# VisualightMicroDIY_038_gnd.net
KiCad netlist of a schematic drawn in EAGLE
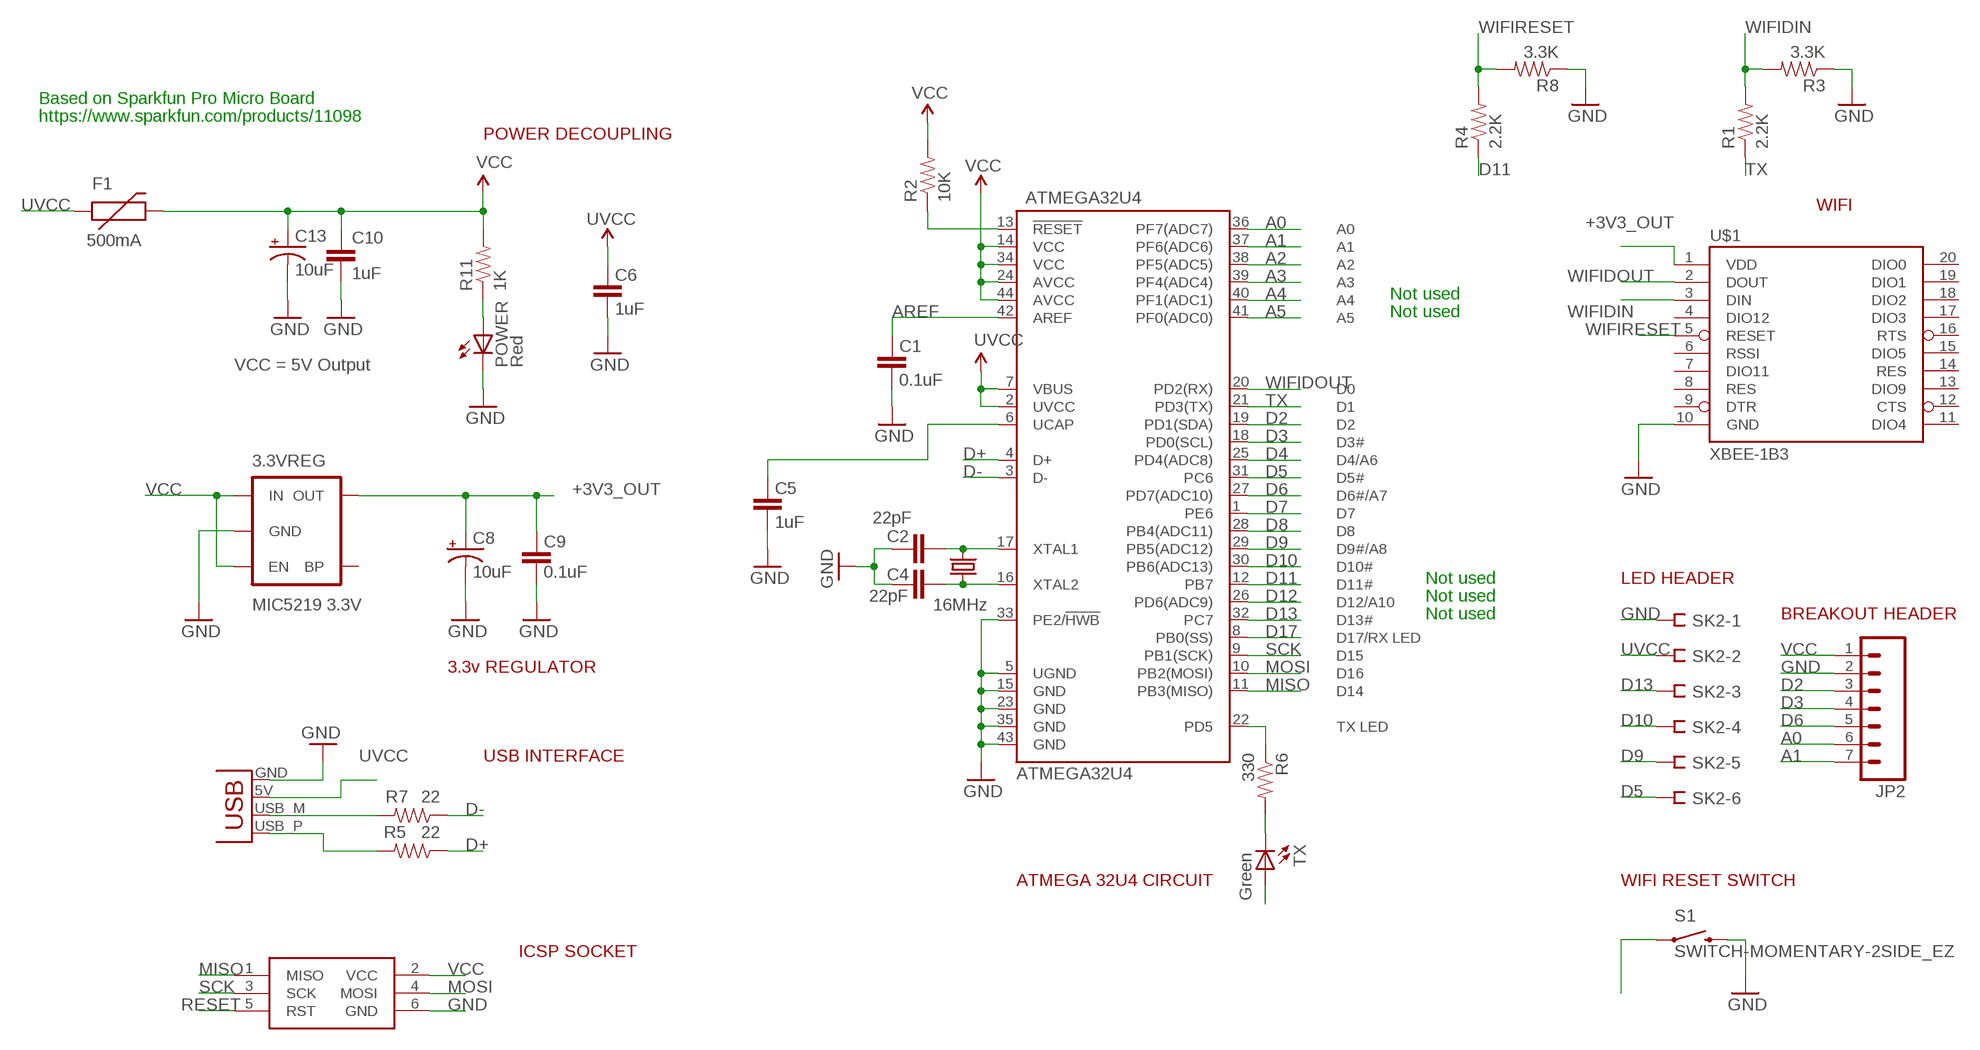
[diagram p0: schematic, sheet 1]

(export (version "E")
  (design (tool "Eeschema 10.0.6"))
  (components
    (comp (ref "3.3VREG")
      (value "MIC5219 3.3V")
      (footprint "eagle-import:SOT23-5")
      (libsource (lib "eagle-import") (part "V_REG_MIC52193.3V"))
    )
    (comp (ref "ATMEGA32U4")
      (value "ATMEGA32U4")
      (footprint "eagle-import:SPARKFUN-DIGITALIC_TQFP44")
      (libsource (lib "eagle-import") (part "ATMEGA32U4TQFP"))
    )
    (comp (ref "C1")
      (value "0.1uF")
      (footprint "eagle-import:0402-CAP")
      (libsource (lib "eagle-import") (part "CAP0402-CAP"))
    )
    (comp (ref "C2")
      (value "22pF")
      (footprint "eagle-import:0402-CAP")
      (libsource (lib "eagle-import") (part "CAP0402-CAP"))
    )
    (comp (ref "C4")
      (value "22pF")
      (footprint "eagle-import:0402-CAP")
      (libsource (lib "eagle-import") (part "CAP0402-CAP"))
    )
    (comp (ref "C5")
      (value "1uF")
      (footprint "eagle-import:0402-CAP")
      (libsource (lib "eagle-import") (part "CAP0402-CAP"))
    )
    (comp (ref "C6")
      (value "1uF")
      (footprint "eagle-import:0402-CAP")
      (libsource (lib "eagle-import") (part "CAP0402-CAP"))
    )
    (comp (ref "C8")
      (value "10uF")
      (footprint "eagle-import:EIA3216")
      (libsource (lib "eagle-import") (part "CAP_POL1206"))
    )
    (comp (ref "C9")
      (value "0.1uF")
      (footprint "eagle-import:0402-CAP")
      (libsource (lib "eagle-import") (part "CAP0402-CAP"))
    )
    (comp (ref "C10")
      (value "1uF")
      (footprint "eagle-import:0402-CAP")
      (libsource (lib "eagle-import") (part "CAP0402-CAP"))
    )
    (comp (ref "C13")
      (value "10uF")
      (footprint "eagle-import:EIA3216")
      (libsource (lib "eagle-import") (part "CAP_POL1206"))
    )
    (comp (ref "F1")
      (value "500mA")
      (footprint "eagle-import:PTC-1206")
      (libsource (lib "eagle-import") (part "PTCSMD"))
    )
    (comp (ref "ISP1")
      (value "AVRISP-6")
      (footprint "eagle-import:AVRISP")
      (libsource (lib "eagle-import") (part "AVRISP-6"))
    )
    (comp (ref "JP2")
      (value "M07")
      (footprint "eagle-import:1X07")
      (libsource (lib "eagle-import") (part "M07"))
    )
    (comp (ref "POWER")
      (value "Red")
      (footprint "eagle-import:LED-0603")
      (libsource (lib "eagle-import") (part "LED0603"))
    )
    (comp (ref "R1")
      (value "2.2K")
      (footprint "eagle-import:0402-RES")
      (libsource (lib "eagle-import") (part "RESISTOR0402-RES"))
    )
    (comp (ref "R2")
      (value "10K")
      (footprint "eagle-import:0402-RES")
      (libsource (lib "eagle-import") (part "RESISTOR0402-RES"))
    )
    (comp (ref "R3")
      (value "3.3K")
      (footprint "eagle-import:0402-RES")
      (libsource (lib "eagle-import") (part "RESISTOR0402-RES"))
    )
    (comp (ref "R4")
      (value "2.2K")
      (footprint "eagle-import:0402-RES")
      (libsource (lib "eagle-import") (part "RESISTOR0402-RES"))
    )
    (comp (ref "R5")
      (value "22")
      (footprint "eagle-import:0402-RES")
      (libsource (lib "eagle-import") (part "RESISTOR0402-RES"))
    )
    (comp (ref "R6")
      (value "330")
      (footprint "eagle-import:0402-RES")
      (libsource (lib "eagle-import") (part "RESISTOR0402-RES"))
    )
    (comp (ref "R7")
      (value "22")
      (footprint "eagle-import:0402-RES")
      (libsource (lib "eagle-import") (part "RESISTOR0402-RES"))
    )
    (comp (ref "R8")
      (value "3.3K")
      (footprint "eagle-import:0402-RES")
      (libsource (lib "eagle-import") (part "RESISTOR0402-RES"))
    )
    (comp (ref "R11")
      (value "1K")
      (footprint "eagle-import:0402-RES")
      (libsource (lib "eagle-import") (part "RESISTOR0402-RES"))
    )
    (comp (ref "S1")
      (value "SWITCH-MOMENTARY-2SIDE_EZ")
      (footprint "eagle-import:TACTILE-PTH-SIDEEZ")
      (libsource (lib "eagle-import") (part "SWITCH-MOMENTARY-2SIDE_EZ"))
    )
    (comp (ref "SK2")
      (value "DF3-06S")
      (footprint "eagle-import:DF3S-06")
      (libsource (lib "eagle-import") (part "DF3-06S"))
    )
    (comp (ref "TX")
      (value "Green")
      (footprint "eagle-import:LED-0603")
      (libsource (lib "eagle-import") (part "LED0603"))
    )
    (comp (ref "U$1")
      (value "XBEE-1B3")
      (footprint "eagle-import:XBEE-SMD")
      (libsource (lib "eagle-import") (part "XBEE-1B3"))
    )
    (comp (ref "X2")
      (value "USBPCB")
      (footprint "eagle-import:USB-A-PCB")
      (libsource (lib "eagle-import") (part "USBPCB"))
    )
    (comp (ref "Y1")
      (value "16MHz")
      (footprint "eagle-import:CRYSTAL-SMD-5X3")
      (libsource (lib "eagle-import") (part "CRYSTAL5X3"))
    )
  )
  (nets
    (net (code "1") (name "/+3V3_OUT") (class "Default")
      (node (ref "3.3VREG") (pin "5") (pinfunction "OUT_5") (pintype "passive"))
      (node (ref "C8") (pin "A") (pinfunction "+_A") (pintype "passive"))
      (node (ref "C9") (pin "2") (pinfunction "2_2") (pintype "passive"))
      (node (ref "U$1") (pin "1") (pinfunction "VDD_1") (pintype "power_in"))
    )
    (net (code "2") (name "/A0") (class "Default")
      (node (ref "ATMEGA32U4") (pin "36") (pinfunction "PF7(ADC7)_36") (pintype "bidirectional"))
      (node (ref "JP2") (pin "6") (pinfunction "6_6") (pintype "passive"))
    )
    (net (code "3") (name "/A1") (class "Default")
      (node (ref "ATMEGA32U4") (pin "37") (pinfunction "PF6(ADC6)_37") (pintype "bidirectional"))
      (node (ref "JP2") (pin "7") (pinfunction "7_7") (pintype "passive"))
    )
    (net (code "4") (name "/A2") (class "Default")
      (node (ref "ATMEGA32U4") (pin "38") (pinfunction "PF5(ADC5)_38") (pintype "bidirectional"))
    )
    (net (code "5") (name "/A3") (class "Default")
      (node (ref "ATMEGA32U4") (pin "39") (pinfunction "PF4(ADC4)_39") (pintype "bidirectional"))
    )
    (net (code "6") (name "/A4") (class "Default")
      (node (ref "ATMEGA32U4") (pin "40") (pinfunction "PF1(ADC1)_40") (pintype "bidirectional"))
    )
    (net (code "7") (name "/A5") (class "Default")
      (node (ref "ATMEGA32U4") (pin "41") (pinfunction "PF0(ADC0)_41") (pintype "bidirectional"))
    )
    (net (code "8") (name "/AREF") (class "Default")
      (node (ref "ATMEGA32U4") (pin "42") (pinfunction "AREF_42") (pintype "bidirectional"))
      (node (ref "C1") (pin "2") (pinfunction "2_2") (pintype "passive"))
    )
    (net (code "9") (name "/D+") (class "Default")
      (node (ref "ATMEGA32U4") (pin "4") (pinfunction "D+_4") (pintype "bidirectional"))
      (node (ref "R5") (pin "1") (pinfunction "1_1") (pintype "passive"))
    )
    (net (code "10") (name "/D-") (class "Default")
      (node (ref "ATMEGA32U4") (pin "3") (pinfunction "D-_3") (pintype "bidirectional"))
      (node (ref "R7") (pin "1") (pinfunction "1_1") (pintype "passive"))
    )
    (net (code "11") (name "/D2") (class "Default")
      (node (ref "ATMEGA32U4") (pin "19") (pinfunction "PD1(SDA)_19") (pintype "bidirectional"))
      (node (ref "JP2") (pin "3") (pinfunction "3_3") (pintype "passive"))
    )
    (net (code "12") (name "/D3") (class "Default")
      (node (ref "ATMEGA32U4") (pin "18") (pinfunction "PD0(SCL)_18") (pintype "bidirectional"))
      (node (ref "JP2") (pin "4") (pinfunction "4_4") (pintype "passive"))
    )
    (net (code "13") (name "/D4") (class "Default")
      (node (ref "ATMEGA32U4") (pin "25") (pinfunction "PD4(ADC8)_25") (pintype "bidirectional"))
    )
    (net (code "14") (name "/D5") (class "Default")
      (node (ref "ATMEGA32U4") (pin "31") (pinfunction "PC6_31") (pintype "bidirectional"))
      (node (ref "SK2") (pin "6") (pinfunction "S_6") (pintype "passive"))
    )
    (net (code "15") (name "/D6") (class "Default")
      (node (ref "ATMEGA32U4") (pin "27") (pinfunction "PD7(ADC10)_27") (pintype "bidirectional"))
      (node (ref "JP2") (pin "5") (pinfunction "5_5") (pintype "passive"))
    )
    (net (code "16") (name "/D7") (class "Default")
      (node (ref "ATMEGA32U4") (pin "1") (pinfunction "PE6_1") (pintype "bidirectional"))
      (node (ref "S1") (pin "1") (pinfunction "1_1") (pintype "passive"))
    )
    (net (code "17") (name "/D8") (class "Default")
      (node (ref "ATMEGA32U4") (pin "28") (pinfunction "PB4(ADC11)_28") (pintype "bidirectional"))
    )
    (net (code "18") (name "/D9") (class "Default")
      (node (ref "ATMEGA32U4") (pin "29") (pinfunction "PB5(ADC12)_29") (pintype "bidirectional"))
      (node (ref "SK2") (pin "5") (pinfunction "S_5") (pintype "passive"))
    )
    (net (code "19") (name "/D10") (class "Default")
      (node (ref "ATMEGA32U4") (pin "30") (pinfunction "PB6(ADC13)_30") (pintype "bidirectional"))
      (node (ref "SK2") (pin "4") (pinfunction "S_4") (pintype "passive"))
    )
    (net (code "20") (name "/D11") (class "Default")
      (node (ref "ATMEGA32U4") (pin "12") (pinfunction "PB7_12") (pintype "bidirectional"))
      (node (ref "R4") (pin "1") (pinfunction "1_1") (pintype "passive"))
    )
    (net (code "21") (name "/D12") (class "Default")
      (node (ref "ATMEGA32U4") (pin "26") (pinfunction "PD6(ADC9)_26") (pintype "bidirectional"))
    )
    (net (code "22") (name "/D13") (class "Default")
      (node (ref "ATMEGA32U4") (pin "32") (pinfunction "PC7_32") (pintype "bidirectional"))
      (node (ref "SK2") (pin "3") (pinfunction "S_3") (pintype "passive"))
    )
    (net (code "23") (name "/D17") (class "Default")
      (node (ref "ATMEGA32U4") (pin "8") (pinfunction "PB0(SS)_8") (pintype "bidirectional"))
    )
    (net (code "24") (name "/MISO") (class "Default")
      (node (ref "ATMEGA32U4") (pin "11") (pinfunction "PB3(MISO)_11") (pintype "bidirectional"))
      (node (ref "ISP1") (pin "1") (pinfunction "MISO_1") (pintype "input"))
    )
    (net (code "25") (name "/MOSI") (class "Default")
      (node (ref "ATMEGA32U4") (pin "10") (pinfunction "PB2(MOSI)_10") (pintype "bidirectional"))
      (node (ref "ISP1") (pin "4") (pinfunction "MOSI_4") (pintype "output"))
    )
    (net (code "26") (name "/RESET") (class "Default")
      (node (ref "ATMEGA32U4") (pin "13") (pinfunction "~{RESET}_13") (pintype "bidirectional"))
      (node (ref "ISP1") (pin "5") (pinfunction "RST_5") (pintype "output"))
      (node (ref "R2") (pin "1") (pinfunction "1_1") (pintype "passive"))
    )
    (net (code "27") (name "/SCK") (class "Default")
      (node (ref "ATMEGA32U4") (pin "9") (pinfunction "PB1(SCK)_9") (pintype "bidirectional"))
      (node (ref "ISP1") (pin "3") (pinfunction "SCK_3") (pintype "output"))
    )
    (net (code "28") (name "/TX") (class "Default")
      (node (ref "ATMEGA32U4") (pin "21") (pinfunction "PD3(TX)_21") (pintype "bidirectional"))
      (node (ref "R1") (pin "1") (pinfunction "1_1") (pintype "passive"))
    )
    (net (code "29") (name "/WIFIDIN") (class "Default")
      (node (ref "R1") (pin "2") (pinfunction "2_2") (pintype "passive"))
      (node (ref "R3") (pin "2") (pinfunction "2_2") (pintype "passive"))
      (node (ref "U$1") (pin "3") (pinfunction "DIN_3") (pintype "input"))
    )
    (net (code "30") (name "/WIFIDOUT") (class "Default")
      (node (ref "ATMEGA32U4") (pin "20") (pinfunction "PD2(RX)_20") (pintype "bidirectional"))
      (node (ref "U$1") (pin "2") (pinfunction "DOUT_2") (pintype "output"))
    )
    (net (code "31") (name "/WIFIRESET") (class "Default")
      (node (ref "R4") (pin "2") (pinfunction "2_2") (pintype "passive"))
      (node (ref "R8") (pin "2") (pinfunction "2_2") (pintype "passive"))
      (node (ref "U$1") (pin "5") (pinfunction "RESET_5") (pintype "input"))
    )
    (net (code "32") (name "GND") (class "Default")
      (node (ref "3.3VREG") (pin "2") (pinfunction "GND_2") (pintype "input"))
      (node (ref "ATMEGA32U4") (pin "15") (pinfunction "GND_15") (pintype "bidirectional"))
      (node (ref "ATMEGA32U4") (pin "23") (pinfunction "GND_23") (pintype "bidirectional"))
      (node (ref "ATMEGA32U4") (pin "33") (pinfunction "PE2/~{HWB}_33") (pintype "bidirectional"))
      (node (ref "ATMEGA32U4") (pin "35") (pinfunction "GND_35") (pintype "bidirectional"))
      (node (ref "ATMEGA32U4") (pin "43") (pinfunction "GND_43") (pintype "bidirectional"))
      (node (ref "ATMEGA32U4") (pin "5") (pinfunction "UGND_5") (pintype "bidirectional"))
      (node (ref "C1") (pin "1") (pinfunction "1_1") (pintype "passive"))
      (node (ref "C10") (pin "2") (pinfunction "2_2") (pintype "passive"))
      (node (ref "C13") (pin "C") (pinfunction "-_C") (pintype "passive"))
      (node (ref "C2") (pin "2") (pinfunction "2_2") (pintype "passive"))
      (node (ref "C4") (pin "2") (pinfunction "2_2") (pintype "passive"))
      (node (ref "C5") (pin "1") (pinfunction "1_1") (pintype "passive"))
      (node (ref "C6") (pin "1") (pinfunction "1_1") (pintype "passive"))
      (node (ref "C8") (pin "C") (pinfunction "-_C") (pintype "passive"))
      (node (ref "C9") (pin "1") (pinfunction "1_1") (pintype "passive"))
      (node (ref "ISP1") (pin "6") (pinfunction "GND_6") (pintype "power_in"))
      (node (ref "JP2") (pin "2") (pinfunction "2_2") (pintype "passive"))
      (node (ref "POWER") (pin "C") (pinfunction "C_C") (pintype "passive"))
      (node (ref "R3") (pin "1") (pinfunction "1_1") (pintype "passive"))
      (node (ref "R8") (pin "1") (pinfunction "1_1") (pintype "passive"))
      (node (ref "S1") (pin "2") (pinfunction "2_2") (pintype "passive"))
      (node (ref "SK2") (pin "1") (pinfunction "S_1") (pintype "passive"))
      (node (ref "U$1") (pin "10") (pinfunction "GND_10") (pintype "power_in"))
      (node (ref "X2") (pin "GND") (pinfunction "GND_GND") (pintype "bidirectional"))
    )
    (net (code "33") (name "Net-(ATMEGA32U4-PD5)") (class "Default")
      (node (ref "ATMEGA32U4") (pin "22") (pinfunction "PD5_22") (pintype "bidirectional"))
      (node (ref "R6") (pin "1") (pinfunction "1_1") (pintype "passive"))
    )
    (net (code "34") (name "Net-(ATMEGA32U4-UCAP)") (class "Default")
      (node (ref "ATMEGA32U4") (pin "6") (pinfunction "UCAP_6") (pintype "bidirectional"))
      (node (ref "C5") (pin "2") (pinfunction "2_2") (pintype "passive"))
    )
    (net (code "35") (name "Net-(ATMEGA32U4-XTAL1)") (class "Default")
      (node (ref "ATMEGA32U4") (pin "17") (pinfunction "XTAL1_17") (pintype "bidirectional"))
      (node (ref "C2") (pin "1") (pinfunction "1_1") (pintype "passive"))
      (node (ref "Y1") (pin "3") (pinfunction "2_3") (pintype "passive"))
    )
    (net (code "36") (name "Net-(ATMEGA32U4-XTAL2)") (class "Default")
      (node (ref "ATMEGA32U4") (pin "16") (pinfunction "XTAL2_16") (pintype "bidirectional"))
      (node (ref "C4") (pin "1") (pinfunction "1_1") (pintype "passive"))
      (node (ref "Y1") (pin "1") (pinfunction "1_1") (pintype "passive"))
    )
    (net (code "37") (name "Net-(POWER-PadA)") (class "Default")
      (node (ref "POWER") (pin "A") (pinfunction "A_A") (pintype "passive"))
      (node (ref "R11") (pin "1") (pinfunction "1_1") (pintype "passive"))
    )
    (net (code "38") (name "Net-(R6-Pad2)") (class "Default")
      (node (ref "R6") (pin "2") (pinfunction "2_2") (pintype "passive"))
      (node (ref "TX") (pin "C") (pinfunction "C_C") (pintype "passive"))
    )
    (net (code "39") (name "Net-(X2-D+)") (class "Default")
      (node (ref "R5") (pin "2") (pinfunction "2_2") (pintype "passive"))
      (node (ref "X2") (pin "USB_P") (pinfunction "D+_USB_P") (pintype "bidirectional"))
    )
    (net (code "40") (name "Net-(X2-D-)") (class "Default")
      (node (ref "R7") (pin "2") (pinfunction "2_2") (pintype "passive"))
      (node (ref "X2") (pin "USB_M") (pinfunction "D-_USB_M") (pintype "bidirectional"))
    )
    (net (code "41") (name "UVCC") (class "Default")
      (node (ref "ATMEGA32U4") (pin "2") (pinfunction "UVCC_2") (pintype "bidirectional"))
      (node (ref "ATMEGA32U4") (pin "7") (pinfunction "VBUS_7") (pintype "bidirectional"))
      (node (ref "C6") (pin "2") (pinfunction "2_2") (pintype "passive"))
      (node (ref "F1") (pin "1") (pinfunction "1_1") (pintype "bidirectional"))
      (node (ref "SK2") (pin "2") (pinfunction "S_2") (pintype "passive"))
      (node (ref "X2") (pin "5V") (pinfunction "VBUS_5V") (pintype "bidirectional"))
    )
    (net (code "42") (name "VCC") (class "Default")
      (node (ref "3.3VREG") (pin "1") (pinfunction "IN_1") (pintype "input"))
      (node (ref "3.3VREG") (pin "3") (pinfunction "EN_3") (pintype "input"))
      (node (ref "ATMEGA32U4") (pin "14") (pinfunction "VCC_14") (pintype "bidirectional"))
      (node (ref "ATMEGA32U4") (pin "24") (pinfunction "AVCC_24") (pintype "bidirectional"))
      (node (ref "ATMEGA32U4") (pin "34") (pinfunction "VCC_34") (pintype "bidirectional"))
      (node (ref "ATMEGA32U4") (pin "44") (pinfunction "AVCC_44") (pintype "bidirectional"))
      (node (ref "C10") (pin "1") (pinfunction "1_1") (pintype "passive"))
      (node (ref "C13") (pin "A") (pinfunction "+_A") (pintype "passive"))
      (node (ref "F1") (pin "2") (pinfunction "2_2") (pintype "bidirectional"))
      (node (ref "ISP1") (pin "2") (pinfunction "VCC_2") (pintype "power_in"))
      (node (ref "JP2") (pin "1") (pinfunction "1_1") (pintype "passive"))
      (node (ref "R11") (pin "2") (pinfunction "2_2") (pintype "passive"))
      (node (ref "R2") (pin "2") (pinfunction "2_2") (pintype "passive"))
      (node (ref "TX") (pin "A") (pinfunction "A_A") (pintype "passive"))
    )
    (net (code "43") (name "unconnected-(3.3VREG-BP-Pad4)") (class "Default")
      (node (ref "3.3VREG") (pin "4") (pinfunction "BP_4") (pintype "input"))
    )
    (net (code "44") (name "unconnected-(U$1-CTS-Pad12)") (class "Default")
      (node (ref "U$1") (pin "12") (pinfunction "CTS_12") (pintype "output"))
    )
    (net (code "45") (name "unconnected-(U$1-DIO0-Pad20)") (class "Default")
      (node (ref "U$1") (pin "20") (pinfunction "DIO0_20") (pintype "bidirectional"))
    )
    (net (code "46") (name "unconnected-(U$1-DIO1-Pad19)") (class "Default")
      (node (ref "U$1") (pin "19") (pinfunction "DIO1_19") (pintype "bidirectional"))
    )
    (net (code "47") (name "unconnected-(U$1-DIO2-Pad18)") (class "Default")
      (node (ref "U$1") (pin "18") (pinfunction "DIO2_18") (pintype "bidirectional"))
    )
    (net (code "48") (name "unconnected-(U$1-DIO3-Pad17)") (class "Default")
      (node (ref "U$1") (pin "17") (pinfunction "DIO3_17") (pintype "bidirectional"))
    )
    (net (code "49") (name "unconnected-(U$1-DIO4-Pad11)") (class "Default")
      (node (ref "U$1") (pin "11") (pinfunction "DIO4_11") (pintype "bidirectional"))
    )
    (net (code "50") (name "unconnected-(U$1-DIO5-Pad15)") (class "Default")
      (node (ref "U$1") (pin "15") (pinfunction "DIO5_15") (pintype "bidirectional"))
    )
    (net (code "51") (name "unconnected-(U$1-DIO9-Pad13)") (class "Default")
      (node (ref "U$1") (pin "13") (pinfunction "DIO9_13") (pintype "bidirectional"))
    )
    (net (code "52") (name "unconnected-(U$1-DIO11-Pad7)") (class "Default")
      (node (ref "U$1") (pin "7") (pinfunction "DIO11_7") (pintype "bidirectional"))
    )
    (net (code "53") (name "unconnected-(U$1-DIO12-Pad4)") (class "Default")
      (node (ref "U$1") (pin "4") (pinfunction "DIO12_4") (pintype "bidirectional"))
    )
    (net (code "54") (name "unconnected-(U$1-DTR-Pad9)") (class "Default")
      (node (ref "U$1") (pin "9") (pinfunction "DTR_9") (pintype "bidirectional"))
    )
    (net (code "55") (name "unconnected-(U$1-RES-Pad8)") (class "Default")
      (node (ref "U$1") (pin "8") (pinfunction "RES_8") (pintype "bidirectional"))
    )
    (net (code "56") (name "unconnected-(U$1-RES-Pad14)") (class "Default")
      (node (ref "U$1") (pin "14") (pinfunction "RES_14") (pintype "bidirectional"))
    )
    (net (code "57") (name "unconnected-(U$1-RSSI-Pad6)") (class "Default")
      (node (ref "U$1") (pin "6") (pinfunction "RSSI_6") (pintype "bidirectional"))
    )
    (net (code "58") (name "unconnected-(U$1-RTS-Pad16)") (class "Default")
      (node (ref "U$1") (pin "16") (pinfunction "RTS_16") (pintype "input"))
    )
  )
)
